# mlogger.net
KiCad netlist of a schematic drawn in EAGLE
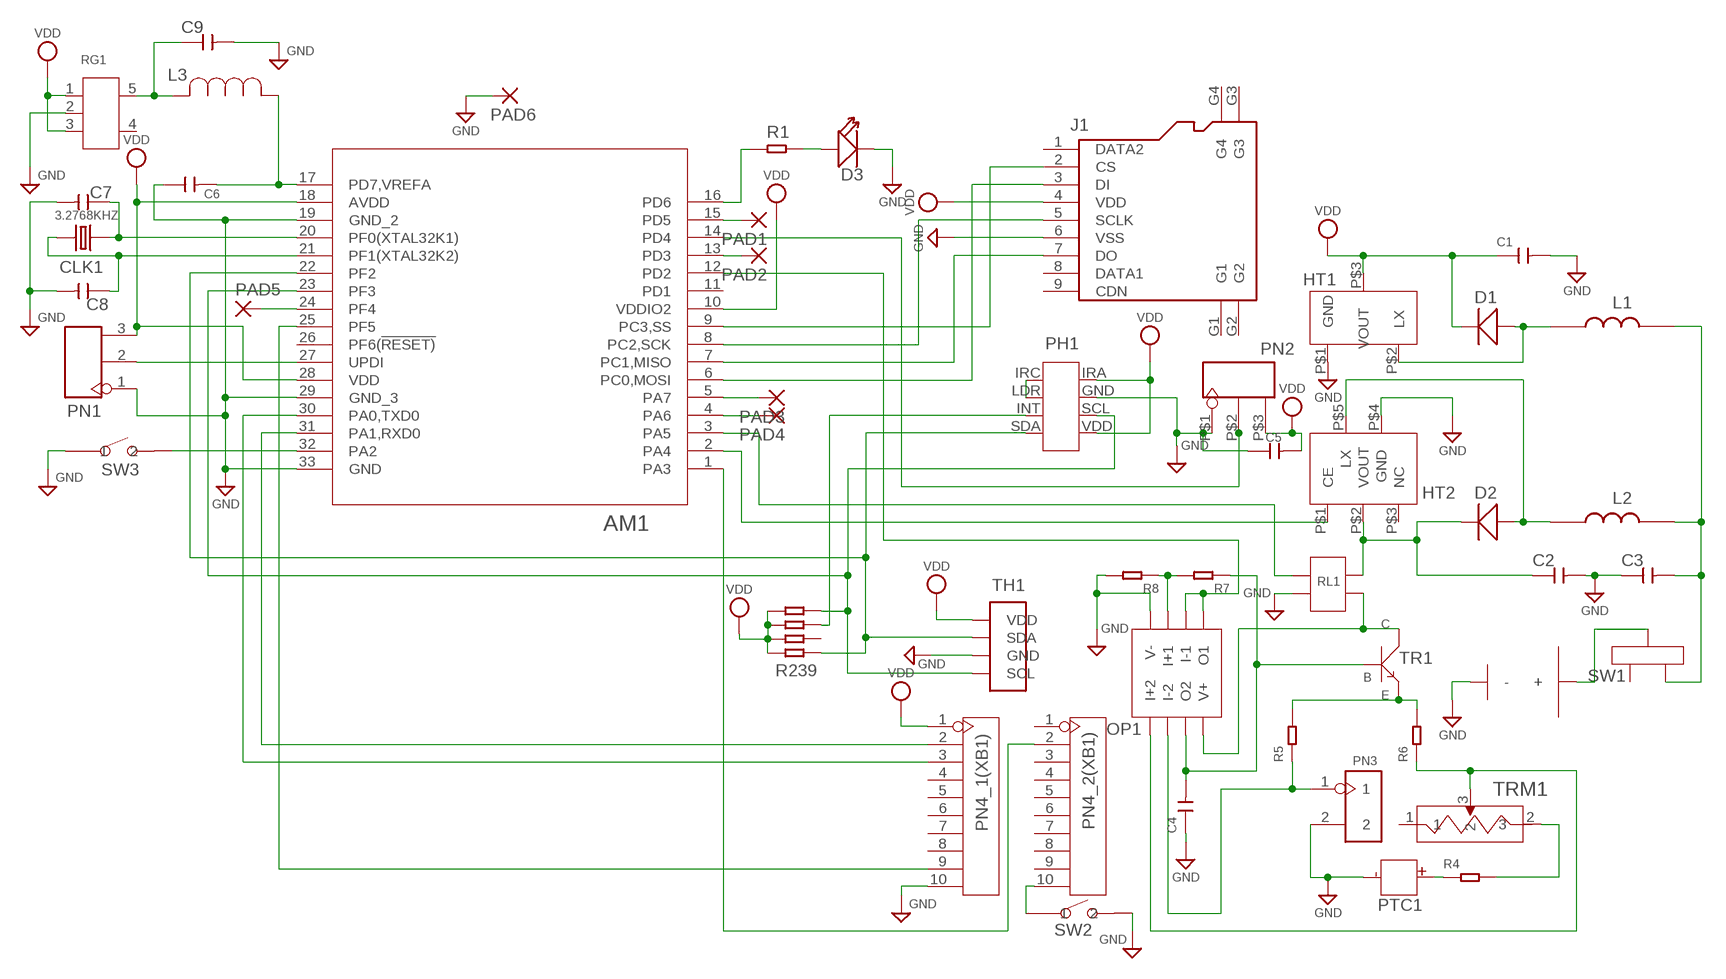
[diagram p0: schematic, sheet 1]

(export (version "E")
  (design (tool "Eeschema 10.0.6"))
  (components
    (comp (ref "AM1")
      (value "AVR64DB32-I/RXBVQFN32_RXB_MCH")
      (footprint "eagle-import:VQFN32_RXB_MCH")
      (fields
        (field (name "MANUFACTURER_PART_NUMBER") "AVR64DB32-I/RXB")
        (field (name "COPYRIGHT") "Copyright (C) 2022 Ultra Librarian. All rights reserved.")
      )
      (libsource (lib "eagle-import") (part "AVR64DB32-I/RXBVQFN32_RXB_MCH"))
    )
    (comp (ref "BB1")
      (value "BH321")
      (footprint "eagle-import:BH321")
      (libsource (lib "eagle-import") (part "BH321"))
    )
    (comp (ref "C1")
      (value "MURATA_0603")
      (footprint "eagle-import:C0603")
      (libsource (lib "eagle-import") (part "MURATA_0603"))
    )
    (comp (ref "C2")
      (value "MURATA_0603")
      (footprint "eagle-import:C0603")
      (libsource (lib "eagle-import") (part "MURATA_0603"))
    )
    (comp (ref "C3")
      (value "MURATA_0603")
      (footprint "eagle-import:C0603")
      (libsource (lib "eagle-import") (part "MURATA_0603"))
    )
    (comp (ref "C4")
      (value "MURATA_0603")
      (footprint "eagle-import:C0603")
      (libsource (lib "eagle-import") (part "MURATA_0603"))
    )
    (comp (ref "C5")
      (value "MURATA_0603")
      (footprint "eagle-import:C0603")
      (libsource (lib "eagle-import") (part "MURATA_0603"))
    )
    (comp (ref "C6")
      (value "MURATA_0603")
      (footprint "eagle-import:C0603")
      (libsource (lib "eagle-import") (part "MURATA_0603"))
    )
    (comp (ref "C7")
      (value "MURATA_0603")
      (footprint "eagle-import:C0603")
      (libsource (lib "eagle-import") (part "MURATA_0603"))
    )
    (comp (ref "C8")
      (value "MURATA_0603")
      (footprint "eagle-import:C0603")
      (libsource (lib "eagle-import") (part "MURATA_0603"))
    )
    (comp (ref "C9")
      (value "MURATA_0603")
      (footprint "eagle-import:C0603")
      (libsource (lib "eagle-import") (part "MURATA_0603"))
    )
    (comp (ref "CLK1")
      (value "3.2768KHZ")
      (footprint "eagle-import:X2-SMD-L2.0X1.2X0.55MM")
      (fields (field (name "MPN") "FC-12M"))
      (libsource (lib "eagle-import") (part "SMD-CRYSTAL-32.768KHZ-12.5PF-20PPM-90K(2P-L2.0X1.2MM)"))
    )
    (comp (ref "D1")
      (value "20V-1A")
      (footprint "eagle-import:SOD-123")
      (fields (field (name "MPN") "B5819W"))
      (libsource (lib "eagle-import") (part "SMD-DIODE-SCHOTTKY-20V-1A(SOD-123)"))
    )
    (comp (ref "D2")
      (value "20V-1A")
      (footprint "eagle-import:SOD-123")
      (fields (field (name "MPN") "B5819W"))
      (libsource (lib "eagle-import") (part "SMD-DIODE-SCHOTTKY-20V-1A(SOD-123)"))
    )
    (comp (ref "D3")
      (value "OSHR1608C1A")
      (footprint "eagle-import:C0603")
      (libsource (lib "eagle-import") (part "OSHR1608C1A"))
    )
    (comp (ref "HT1")
      (value "HT77XXSOT23")
      (footprint "eagle-import:HT77XXSOT23")
      (libsource (lib "eagle-import") (part "HT77XXSOT23"))
    )
    (comp (ref "HT2")
      (value "HT77XXSOT25")
      (footprint "eagle-import:HT77XXSOT25")
      (libsource (lib "eagle-import") (part "HT77XXSOT25"))
    )
    (comp (ref "J1")
      (value "MICROSD-9P")
      (footprint "eagle-import:MICRO-SD9+4P-SMD-16.1X14.5X1.85MM")
      (libsource (lib "eagle-import") (part "MICRO-SD-CARD-HOLDER-9P"))
    )
    (comp (ref "L1")
      (value "303010168_47UM_5X5MM")
      (footprint "eagle-import:L2018")
      (libsource (lib "eagle-import") (part "303010168_47UM_5X5MM"))
    )
    (comp (ref "L2")
      (value "303010168_47UM_5X5MM")
      (footprint "eagle-import:L2018")
      (libsource (lib "eagle-import") (part "303010168_47UM_5X5MM"))
    )
    (comp (ref "L3")
      (value "LBR2012T100KIND_TAIYO_LBR2012_TAY")
      (footprint "eagle-import:IND_TAIYO_LBR2012_TAY")
      (libsource (lib "eagle-import") (part "LBR2012T100KIND_TAIYO_LBR2012_TAY"))
    )
    (comp (ref "OP1")
      (value "NJM4565")
      (footprint "eagle-import:NJM4565")
      (libsource (lib "eagle-import") (part "NJM4565"))
    )
    (comp (ref "PAD1")
      (value "1,6/0,8")
      (footprint "eagle-import:1,6_0,8")
      (libsource (lib "eagle-import") (part "1,6/0,8"))
    )
    (comp (ref "PAD2")
      (value "1,6/0,8")
      (footprint "eagle-import:1,6_0,8")
      (libsource (lib "eagle-import") (part "1,6/0,8"))
    )
    (comp (ref "PAD3")
      (value "1,6/0,8")
      (footprint "eagle-import:1,6_0,8")
      (libsource (lib "eagle-import") (part "1,6/0,8"))
    )
    (comp (ref "PAD4")
      (value "1,6/0,8")
      (footprint "eagle-import:1,6_0,8")
      (libsource (lib "eagle-import") (part "1,6/0,8"))
    )
    (comp (ref "PAD5")
      (value "1,6/0,8")
      (footprint "eagle-import:1,6_0,8")
      (libsource (lib "eagle-import") (part "1,6/0,8"))
    )
    (comp (ref "PAD6")
      (value "1,6/0,8")
      (footprint "eagle-import:1,6_0,8")
      (libsource (lib "eagle-import") (part "1,6/0,8"))
    )
    (comp (ref "PH1")
      (value "VCNL4030X01")
      (footprint "eagle-import:VCNL4030X01")
      (libsource (lib "eagle-import") (part "VCNL4030X01"))
    )
    (comp (ref "PN1")
      (value "3p-2.54")
      (footprint "eagle-import:H3-2.54")
      (libsource (lib "eagle-import") (part "DIP-BLACK-MALE-HEADER-VERT(3P-2.54)"))
    )
    (comp (ref "PN2")
      (value "B3B-PH-K-S")
      (footprint "eagle-import:B3B-PH-K-S")
      (libsource (lib "eagle-import") (part "B3B-PH-K-S"))
    )
    (comp (ref "PN3")
      (value "2p-2.54")
      (footprint "eagle-import:H2-2.54")
      (fields (field (name "MPN") "RF130-1023ABS0741"))
      (libsource (lib "eagle-import") (part "DIP-BLACK-ROUND-FEMALE-HEADER-VERT(2P-2.54)"))
    )
    (comp (ref "PN4_1(XB1)")
      (value "10p-2.0")
      (footprint "eagle-import:H10-2.0")
      (fields (field (name "MPN") "F243-1110A1BSUA1"))
      (libsource (lib "eagle-import") (part "DIP-BLACK-FEMALE-HEADER-VERT(10P-2.0)"))
    )
    (comp (ref "PN4_2(XB1)")
      (value "10p-2.0")
      (footprint "eagle-import:H10-2.0")
      (fields (field (name "MPN") "F243-1110A1BSUA1"))
      (libsource (lib "eagle-import") (part "DIP-BLACK-FEMALE-HEADER-VERT(10P-2.0)"))
    )
    (comp (ref "PTC1")
      (value "TFPT1206")
      (footprint "eagle-import:TFPT1206")
      (libsource (lib "eagle-import") (part "TFPT1206"))
    )
    (comp (ref "R1")
      (value "RES_0603")
      (footprint "eagle-import:R0603")
      (libsource (lib "eagle-import") (part "RES_0603"))
    )
    (comp (ref "R4")
      (value "RES_0603")
      (footprint "eagle-import:R0603")
      (libsource (lib "eagle-import") (part "RES_0603"))
    )
    (comp (ref "R5")
      (value "RES_0603")
      (footprint "eagle-import:R0603")
      (libsource (lib "eagle-import") (part "RES_0603"))
    )
    (comp (ref "R6")
      (value "RES_0603")
      (footprint "eagle-import:R0603")
      (libsource (lib "eagle-import") (part "RES_0603"))
    )
    (comp (ref "R7")
      (value "RES_0603")
      (footprint "eagle-import:R0603")
      (libsource (lib "eagle-import") (part "RES_0603"))
    )
    (comp (ref "R8")
      (value "RES_0603")
      (footprint "eagle-import:R0603")
      (libsource (lib "eagle-import") (part "RES_0603"))
    )
    (comp (ref "R239")
      (value "R1005X4")
      (footprint "eagle-import:R1005X4")
      (libsource (lib "eagle-import") (part "R1005X4"))
    )
    (comp (ref "RG1")
      (value "TCR2EF20SOT-25___(SMV)_TOS")
      (footprint "eagle-import:SOT-25___(SMV)_TOS")
      (libsource (lib "eagle-import") (part "TCR2EF20SOT-25___(SMV)_TOS"))
    )
    (comp (ref "RL1")
      (value "CPC1002N")
      (footprint "eagle-import:CPC1002N")
      (libsource (lib "eagle-import") (part "CPC1002N"))
    )
    (comp (ref "SW1")
      (value "SS-12D00G3")
      (footprint "eagle-import:SS-12D00G3")
      (libsource (lib "eagle-import") (part "SS-12D00G3"))
    )
    (comp (ref "SW2")
      (value "TVAF06-A020B-R")
      (footprint "eagle-import:TVAF06-A020B-R")
      (libsource (lib "eagle-import") (part "TVAF06-A020B-R"))
    )
    (comp (ref "SW3")
      (value "TVAF06-A020B-R")
      (footprint "eagle-import:TVAF06-A020B-R")
      (libsource (lib "eagle-import") (part "TVAF06-A020B-R"))
    )
    (comp (ref "TH1")
      (value "AHT20")
      (footprint "eagle-import:AHT20")
      (libsource (lib "eagle-import") (part "AHT20"))
    )
    (comp (ref "TR1")
      (value "MMBTA42")
      (footprint "eagle-import:MMBTA42")
      (libsource (lib "eagle-import") (part "MMBTA42"))
    )
    (comp (ref "TRM1")
      (value "TC33X-1-103EIND_1-103E-L")
      (footprint "eagle-import:IND_1-103E-L")
      (libsource (lib "eagle-import") (part "TC33X-1-103EIND_1-103E-L"))
    )
  )
  (nets
    (net (code "1") (name "GND") (class "Default")
      (node (ref "AM1") (pin "19") (pinfunction "GND_2_19") (pintype "passive"))
      (node (ref "AM1") (pin "29") (pinfunction "GND_3_29") (pintype "passive"))
      (node (ref "AM1") (pin "33") (pinfunction "GND_33") (pintype "passive"))
      (node (ref "BB1") (pin "V-") (pinfunction "-_V-") (pintype "bidirectional"))
      (node (ref "C1") (pin "2") (pinfunction "2_2") (pintype "passive"))
      (node (ref "C2") (pin "2") (pinfunction "2_2") (pintype "passive"))
      (node (ref "C3") (pin "1") (pinfunction "1_1") (pintype "passive"))
      (node (ref "C4") (pin "1") (pinfunction "1_1") (pintype "passive"))
      (node (ref "C5") (pin "1") (pinfunction "1_1") (pintype "passive"))
      (node (ref "C6") (pin "1") (pinfunction "1_1") (pintype "passive"))
      (node (ref "C7") (pin "2") (pinfunction "2_2") (pintype "passive"))
      (node (ref "C8") (pin "2") (pinfunction "2_2") (pintype "passive"))
      (node (ref "C9") (pin "2") (pinfunction "2_2") (pintype "passive"))
      (node (ref "D3") (pin "2") (pinfunction "-_2") (pintype "passive"))
      (node (ref "HT1") (pin "P$1") (pinfunction "GND_P$1") (pintype "bidirectional"))
      (node (ref "HT2") (pin "P$4") (pinfunction "GND_P$4") (pintype "bidirectional"))
      (node (ref "J1") (pin "6") (pinfunction "VSS_6") (pintype "bidirectional"))
      (node (ref "OP1") (pin "P$4") (pinfunction "V-_P$4") (pintype "bidirectional"))
      (node (ref "PAD6") (pin "1") (pinfunction "P_1") (pintype "passive"))
      (node (ref "PH1") (pin "GND") (pinfunction "GND_GND") (pintype "bidirectional"))
      (node (ref "PN1") (pin "1") (pinfunction "P$1_1") (pintype "bidirectional"))
      (node (ref "PN2") (pin "P$1") (pinfunction "P$1_P$1") (pintype "bidirectional"))
      (node (ref "PN3") (pin "2") (pinfunction "2_2") (pintype "bidirectional"))
      (node (ref "PN4_1(XB1)") (pin "10") (pinfunction "10_10") (pintype "bidirectional"))
      (node (ref "PTC1") (pin "P$1") (pinfunction "P$1_P$1") (pintype "bidirectional"))
      (node (ref "R8") (pin "2") (pinfunction "2_2") (pintype "passive"))
      (node (ref "RG1") (pin "2") (pinfunction "2_2") (pintype "passive"))
      (node (ref "RL1") (pin "GND") (pinfunction "GND_GND") (pintype "bidirectional"))
      (node (ref "SW2") (pin "P$2") (pinfunction "2_P$2") (pintype "bidirectional"))
      (node (ref "SW3") (pin "P$1") (pinfunction "1_P$1") (pintype "bidirectional"))
      (node (ref "TH1") (pin "P$5") (pinfunction "GND_P$5") (pintype "bidirectional"))
    )
    (net (code "2") (name "Net-(AM1-PA0,TXD0)") (class "Default")
      (node (ref "AM1") (pin "30") (pinfunction "PA0,TXD0_30") (pintype "bidirectional"))
      (node (ref "PN4_1(XB1)") (pin "3") (pinfunction "3_3") (pintype "bidirectional"))
    )
    (net (code "3") (name "Net-(AM1-PA1,RXD0)") (class "Default")
      (node (ref "AM1") (pin "31") (pinfunction "PA1,RXD0_31") (pintype "bidirectional"))
      (node (ref "PN4_1(XB1)") (pin "2") (pinfunction "2_2") (pintype "bidirectional"))
    )
    (net (code "4") (name "Net-(AM1-PA2)") (class "Default")
      (node (ref "AM1") (pin "32") (pinfunction "PA2_32") (pintype "bidirectional"))
      (node (ref "SW3") (pin "P$2") (pinfunction "2_P$2") (pintype "bidirectional"))
    )
    (net (code "5") (name "Net-(AM1-PA3)") (class "Default")
      (node (ref "AM1") (pin "1") (pinfunction "PA3_1") (pintype "bidirectional"))
      (node (ref "PN4_2(XB1)") (pin "2") (pinfunction "2_2") (pintype "bidirectional"))
    )
    (net (code "6") (name "Net-(AM1-PA4)") (class "Default")
      (node (ref "AM1") (pin "2") (pinfunction "PA4_2") (pintype "bidirectional"))
      (node (ref "HT2") (pin "P$1") (pinfunction "CE_P$1") (pintype "bidirectional"))
    )
    (net (code "7") (name "Net-(AM1-PA5)") (class "Default")
      (node (ref "AM1") (pin "3") (pinfunction "PA5_3") (pintype "bidirectional"))
      (node (ref "RL1") (pin "+") (pinfunction "+_+") (pintype "bidirectional"))
    )
    (net (code "8") (name "Net-(AM1-PA6)") (class "Default")
      (node (ref "AM1") (pin "4") (pinfunction "PA6_4") (pintype "bidirectional"))
      (node (ref "PAD4") (pin "1") (pinfunction "P_1") (pintype "passive"))
    )
    (net (code "9") (name "Net-(AM1-PA7)") (class "Default")
      (node (ref "AM1") (pin "5") (pinfunction "PA7_5") (pintype "bidirectional"))
      (node (ref "PAD3") (pin "1") (pinfunction "P_1") (pintype "passive"))
    )
    (net (code "10") (name "Net-(AM1-PC0,MOSI)") (class "Default")
      (node (ref "AM1") (pin "6") (pinfunction "PC0,MOSI_6") (pintype "bidirectional"))
      (node (ref "J1") (pin "3") (pinfunction "DI_3") (pintype "bidirectional"))
    )
    (net (code "11") (name "Net-(AM1-PC1,MISO)") (class "Default")
      (node (ref "AM1") (pin "7") (pinfunction "PC1,MISO_7") (pintype "bidirectional"))
      (node (ref "J1") (pin "7") (pinfunction "DO_7") (pintype "bidirectional"))
    )
    (net (code "12") (name "Net-(AM1-PC2,SCK)") (class "Default")
      (node (ref "AM1") (pin "8") (pinfunction "PC2,SCK_8") (pintype "bidirectional"))
      (node (ref "J1") (pin "5") (pinfunction "SCLK_5") (pintype "bidirectional"))
    )
    (net (code "13") (name "Net-(AM1-PC3,SS)") (class "Default")
      (node (ref "AM1") (pin "9") (pinfunction "PC3,SS_9") (pintype "bidirectional"))
      (node (ref "J1") (pin "2") (pinfunction "CS_2") (pintype "bidirectional"))
    )
    (net (code "14") (name "Net-(AM1-PD2)") (class "Default")
      (node (ref "AM1") (pin "12") (pinfunction "PD2_12") (pintype "bidirectional"))
      (node (ref "OP1") (pin "P$1") (pinfunction "O1_P$1") (pintype "bidirectional"))
      (node (ref "OP1") (pin "P$2") (pinfunction "I-1_P$2") (pintype "bidirectional"))
    )
    (net (code "15") (name "Net-(AM1-PD3)") (class "Default")
      (node (ref "AM1") (pin "13") (pinfunction "PD3_13") (pintype "bidirectional"))
      (node (ref "PAD2") (pin "1") (pinfunction "P_1") (pintype "passive"))
    )
    (net (code "16") (name "Net-(AM1-PD4)") (class "Default")
      (node (ref "AM1") (pin "14") (pinfunction "PD4_14") (pintype "bidirectional"))
      (node (ref "PN2") (pin "P$2") (pinfunction "P$2_P$2") (pintype "bidirectional"))
    )
    (net (code "17") (name "Net-(AM1-PD5)") (class "Default")
      (node (ref "AM1") (pin "15") (pinfunction "PD5_15") (pintype "bidirectional"))
      (node (ref "PAD1") (pin "1") (pinfunction "P_1") (pintype "passive"))
    )
    (net (code "18") (name "Net-(AM1-PD6)") (class "Default")
      (node (ref "AM1") (pin "16") (pinfunction "PD6_16") (pintype "bidirectional"))
      (node (ref "R1") (pin "2") (pinfunction "2_2") (pintype "passive"))
    )
    (net (code "19") (name "Net-(AM1-PD7,VREFA)") (class "Default")
      (node (ref "AM1") (pin "17") (pinfunction "PD7,VREFA_17") (pintype "bidirectional"))
      (node (ref "C6") (pin "2") (pinfunction "2_2") (pintype "passive"))
      (node (ref "L3") (pin "1") (pinfunction "1_1") (pintype "passive"))
    )
    (net (code "20") (name "Net-(AM1-PF0(XTAL32K1))") (class "Default")
      (node (ref "AM1") (pin "20") (pinfunction "PF0(XTAL32K1)_20") (pintype "bidirectional"))
      (node (ref "C7") (pin "1") (pinfunction "1_1") (pintype "passive"))
      (node (ref "CLK1") (pin "1") (pinfunction "1_1") (pintype "passive"))
    )
    (net (code "21") (name "Net-(AM1-PF1(XTAL32K2))") (class "Default")
      (node (ref "AM1") (pin "21") (pinfunction "PF1(XTAL32K2)_21") (pintype "bidirectional"))
      (node (ref "C8") (pin "1") (pinfunction "1_1") (pintype "passive"))
      (node (ref "CLK1") (pin "2") (pinfunction "2_2") (pintype "passive"))
    )
    (net (code "22") (name "Net-(AM1-PF2)") (class "Default")
      (node (ref "AM1") (pin "22") (pinfunction "PF2_22") (pintype "bidirectional"))
      (node (ref "PH1") (pin "SDA") (pinfunction "SDA_SDA") (pintype "bidirectional"))
      (node (ref "R239") (pin "8") (pinfunction "8_8") (pintype "passive"))
      (node (ref "TH1") (pin "P$4") (pinfunction "SDA_P$4") (pintype "bidirectional"))
    )
    (net (code "23") (name "Net-(AM1-PF3)") (class "Default")
      (node (ref "AM1") (pin "23") (pinfunction "PF3_23") (pintype "bidirectional"))
      (node (ref "PH1") (pin "SCL") (pinfunction "SCL_SCL") (pintype "bidirectional"))
      (node (ref "R239") (pin "2") (pinfunction "2_2") (pintype "passive"))
      (node (ref "TH1") (pin "P$3") (pinfunction "SCL_P$3") (pintype "bidirectional"))
    )
    (net (code "24") (name "Net-(AM1-PF4)") (class "Default")
      (node (ref "AM1") (pin "24") (pinfunction "PF4_24") (pintype "bidirectional"))
      (node (ref "PAD5") (pin "1") (pinfunction "P_1") (pintype "passive"))
    )
    (net (code "25") (name "Net-(AM1-PF5)") (class "Default")
      (node (ref "AM1") (pin "25") (pinfunction "PF5_25") (pintype "bidirectional"))
      (node (ref "PN4_1(XB1)") (pin "9") (pinfunction "9_9") (pintype "bidirectional"))
    )
    (net (code "26") (name "Net-(AM1-UPDI)") (class "Default")
      (node (ref "AM1") (pin "27") (pinfunction "UPDI_27") (pintype "bidirectional"))
      (node (ref "PN1") (pin "2") (pinfunction "P$2_2") (pintype "bidirectional"))
    )
    (net (code "27") (name "Net-(BB1-+)") (class "Default")
      (node (ref "BB1") (pin "V+") (pinfunction "+_V+") (pintype "bidirectional"))
      (node (ref "SW1") (pin "P$1") (pinfunction "P2_P$1") (pintype "bidirectional"))
    )
    (net (code "28") (name "Net-(C9-Pad1)") (class "Default")
      (node (ref "C9") (pin "1") (pinfunction "1_1") (pintype "passive"))
      (node (ref "L3") (pin "2") (pinfunction "2_2") (pintype "passive"))
      (node (ref "RG1") (pin "5") (pinfunction "5_5") (pintype "power_in"))
    )
    (net (code "29") (name "Net-(D3-+)") (class "Default")
      (node (ref "D3") (pin "1") (pinfunction "+_1") (pintype "passive"))
      (node (ref "R1") (pin "1") (pinfunction "1_1") (pintype "passive"))
    )
    (net (code "30") (name "Net-(HT1-LX)") (class "Default")
      (node (ref "D1") (pin "+") (pinfunction "+_+") (pintype "passive"))
      (node (ref "HT1") (pin "P$2") (pinfunction "LX_P$2") (pintype "bidirectional"))
      (node (ref "L1") (pin "P$1") (pinfunction "P$1_P$1") (pintype "passive"))
    )
    (net (code "31") (name "Net-(HT2-LX)") (class "Default")
      (node (ref "D2") (pin "+") (pinfunction "+_+") (pintype "passive"))
      (node (ref "HT2") (pin "P$5") (pinfunction "LX_P$5") (pintype "bidirectional"))
      (node (ref "L2") (pin "P$1") (pinfunction "P$1_P$1") (pintype "passive"))
    )
    (net (code "32") (name "Net-(HT2-VOUT)") (class "Default")
      (node (ref "C2") (pin "1") (pinfunction "1_1") (pintype "passive"))
      (node (ref "D2") (pin "-") (pinfunction "-_-") (pintype "passive"))
      (node (ref "HT2") (pin "P$2") (pinfunction "VOUT_P$2") (pintype "bidirectional"))
      (node (ref "RL1") (pin "DC+") (pinfunction "DC+_DC+") (pintype "bidirectional"))
    )
    (net (code "33") (name "Net-(OP1-I+1)") (class "Default")
      (node (ref "OP1") (pin "P$3") (pinfunction "I+1_P$3") (pintype "bidirectional"))
      (node (ref "R7") (pin "2") (pinfunction "2_2") (pintype "passive"))
      (node (ref "R8") (pin "1") (pinfunction "1_1") (pintype "passive"))
    )
    (net (code "34") (name "Net-(OP1-I+2)") (class "Default")
      (node (ref "OP1") (pin "P$5") (pinfunction "I+2_P$5") (pintype "bidirectional"))
      (node (ref "R6") (pin "1") (pinfunction "1_1") (pintype "passive"))
      (node (ref "TRM1") (pin "3") (pinfunction "2_3") (pintype "passive"))
    )
    (net (code "35") (name "Net-(OP1-I-2)") (class "Default")
      (node (ref "OP1") (pin "P$6") (pinfunction "I-2_P$6") (pintype "bidirectional"))
      (node (ref "PN3") (pin "1") (pinfunction "1_1") (pintype "bidirectional"))
      (node (ref "R5") (pin "1") (pinfunction "1_1") (pintype "passive"))
    )
    (net (code "36") (name "Net-(OP1-O2)") (class "Default")
      (node (ref "C4") (pin "2") (pinfunction "2_2") (pintype "passive"))
      (node (ref "OP1") (pin "P$7") (pinfunction "O2_P$7") (pintype "bidirectional"))
      (node (ref "R7") (pin "1") (pinfunction "1_1") (pintype "passive"))
      (node (ref "TR1") (pin "P$1") (pinfunction "P$1_P$1") (pintype "bidirectional"))
    )
    (net (code "37") (name "Net-(OP1-V+)") (class "Default")
      (node (ref "OP1") (pin "P$8") (pinfunction "V+_P$8") (pintype "bidirectional"))
      (node (ref "RL1") (pin "DC-") (pinfunction "DC-_DC-") (pintype "bidirectional"))
      (node (ref "TR1") (pin "P$3") (pinfunction "C_P$3") (pintype "bidirectional"))
    )
    (net (code "38") (name "Net-(PH1-PadINT)") (class "Default")
      (node (ref "PH1") (pin "INT") (pinfunction "INT_INT") (pintype "bidirectional"))
      (node (ref "R239") (pin "4") (pinfunction "4_4") (pintype "passive"))
    )
    (net (code "39") (name "Net-(PH1-PadIRC)") (class "Default")
      (node (ref "PH1") (pin "IRC") (pinfunction "IRC_IRC") (pintype "bidirectional"))
      (node (ref "PH1") (pin "LDR") (pinfunction "LDR_LDR") (pintype "bidirectional"))
    )
    (net (code "40") (name "Net-(PTC1-PadP$2)") (class "Default")
      (node (ref "PTC1") (pin "P$2") (pinfunction "P$2_P$2") (pintype "bidirectional"))
      (node (ref "R4") (pin "1") (pinfunction "1_1") (pintype "passive"))
    )
    (net (code "41") (name "Net-(R5-Pad2)") (class "Default")
      (node (ref "R5") (pin "2") (pinfunction "2_2") (pintype "passive"))
      (node (ref "R6") (pin "2") (pinfunction "2_2") (pintype "passive"))
      (node (ref "TR1") (pin "P$2") (pinfunction "P$2_P$2") (pintype "bidirectional"))
    )
    (net (code "42") (name "Net-(SW1-P1)") (class "Default")
      (node (ref "C3") (pin "2") (pinfunction "2_2") (pintype "passive"))
      (node (ref "L1") (pin "P$2") (pinfunction "P$2_P$2") (pintype "passive"))
      (node (ref "L2") (pin "P$2") (pinfunction "P$2_P$2") (pintype "passive"))
      (node (ref "SW1") (pin "P$2") (pinfunction "P1_P$2") (pintype "bidirectional"))
    )
    (net (code "43") (name "Net-(SW2-1)") (class "Default")
      (node (ref "PN4_2(XB1)") (pin "10") (pinfunction "10_10") (pintype "bidirectional"))
      (node (ref "SW2") (pin "P$1") (pinfunction "1_P$1") (pintype "bidirectional"))
    )
    (net (code "44") (name "Net-(TRM1-3)") (class "Default")
      (node (ref "R4") (pin "2") (pinfunction "2_2") (pintype "passive"))
      (node (ref "TRM1") (pin "2") (pinfunction "3_2") (pintype "passive"))
    )
    (net (code "45") (name "VDD") (class "Default")
      (node (ref "AM1") (pin "10") (pinfunction "VDDIO2_10") (pintype "power_in"))
      (node (ref "AM1") (pin "18") (pinfunction "AVDD_18") (pintype "power_in"))
      (node (ref "AM1") (pin "28") (pinfunction "VDD_28") (pintype "power_in"))
      (node (ref "C1") (pin "1") (pinfunction "1_1") (pintype "passive"))
      (node (ref "C5") (pin "2") (pinfunction "2_2") (pintype "passive"))
      (node (ref "D1") (pin "-") (pinfunction "-_-") (pintype "passive"))
      (node (ref "HT1") (pin "P$3") (pinfunction "VOUT_P$3") (pintype "bidirectional"))
      (node (ref "J1") (pin "4") (pinfunction "VDD_4") (pintype "bidirectional"))
      (node (ref "PH1") (pin "IRA") (pinfunction "IRA_IRA") (pintype "bidirectional"))
      (node (ref "PH1") (pin "VDD") (pinfunction "VDD_VDD") (pintype "bidirectional"))
      (node (ref "PN1") (pin "3") (pinfunction "P$3_3") (pintype "bidirectional"))
      (node (ref "PN2") (pin "P$3") (pinfunction "P$3_P$3") (pintype "bidirectional"))
      (node (ref "PN4_1(XB1)") (pin "1") (pinfunction "1_1") (pintype "bidirectional"))
      (node (ref "R239") (pin "1") (pinfunction "1_1") (pintype "passive"))
      (node (ref "R239") (pin "3") (pinfunction "3_3") (pintype "passive"))
      (node (ref "R239") (pin "5") (pinfunction "5_5") (pintype "passive"))
      (node (ref "R239") (pin "7") (pinfunction "7_7") (pintype "passive"))
      (node (ref "RG1") (pin "1") (pinfunction "1_1") (pintype "power_in"))
      (node (ref "RG1") (pin "3") (pinfunction "3_3") (pintype "passive"))
      (node (ref "TH1") (pin "P$2") (pinfunction "VDD_P$2") (pintype "bidirectional"))
    )
    (net (code "46") (name "unconnected-(AM1-PD1-Pad11)") (class "Default")
      (node (ref "AM1") (pin "11") (pinfunction "PD1_11") (pintype "bidirectional"))
    )
    (net (code "47") (name "unconnected-(AM1-PF6(~{RESET})-Pad26)") (class "Default")
      (node (ref "AM1") (pin "26") (pinfunction "PF6(~{RESET})_26") (pintype "bidirectional"))
    )
    (net (code "48") (name "unconnected-(HT2-NC-PadP$3)") (class "Default")
      (node (ref "HT2") (pin "P$3") (pinfunction "NC_P$3") (pintype "bidirectional"))
    )
    (net (code "49") (name "unconnected-(J1-CDN-Pad9)") (class "Default")
      (node (ref "J1") (pin "9") (pinfunction "CDN_9") (pintype "bidirectional"))
    )
    (net (code "50") (name "unconnected-(J1-DATA1-Pad8)") (class "Default")
      (node (ref "J1") (pin "8") (pinfunction "DATA1_8") (pintype "bidirectional"))
    )
    (net (code "51") (name "unconnected-(J1-DATA2-Pad1)") (class "Default")
      (node (ref "J1") (pin "1") (pinfunction "DATA2_1") (pintype "bidirectional"))
    )
    (net (code "52") (name "unconnected-(J1-PadG1)") (class "Default")
      (node (ref "J1") (pin "G1") (pinfunction "G1_G1") (pintype "bidirectional"))
    )
    (net (code "53") (name "unconnected-(J1-PadG2)") (class "Default")
      (node (ref "J1") (pin "G2") (pinfunction "G2_G2") (pintype "bidirectional"))
    )
    (net (code "54") (name "unconnected-(J1-PadG3)") (class "Default")
      (node (ref "J1") (pin "G3") (pinfunction "G3_G3") (pintype "bidirectional"))
    )
    (net (code "55") (name "unconnected-(J1-PadG4)") (class "Default")
      (node (ref "J1") (pin "G4") (pinfunction "G4_G4") (pintype "bidirectional"))
    )
    (net (code "56") (name "unconnected-(PN4_1(XB1)-Pad4)") (class "Default")
      (node (ref "PN4_1(XB1)") (pin "4") (pinfunction "4_4") (pintype "bidirectional"))
    )
    (net (code "57") (name "unconnected-(PN4_1(XB1)-Pad5)") (class "Default")
      (node (ref "PN4_1(XB1)") (pin "5") (pinfunction "5_5") (pintype "bidirectional"))
    )
    (net (code "58") (name "unconnected-(PN4_1(XB1)-Pad6)") (class "Default")
      (node (ref "PN4_1(XB1)") (pin "6") (pinfunction "6_6") (pintype "bidirectional"))
    )
    (net (code "59") (name "unconnected-(PN4_1(XB1)-Pad7)") (class "Default")
      (node (ref "PN4_1(XB1)") (pin "7") (pinfunction "7_7") (pintype "bidirectional"))
    )
    (net (code "60") (name "unconnected-(PN4_1(XB1)-Pad8)") (class "Default")
      (node (ref "PN4_1(XB1)") (pin "8") (pinfunction "8_8") (pintype "bidirectional"))
    )
    (net (code "61") (name "unconnected-(PN4_2(XB1)-Pad1)") (class "Default")
      (node (ref "PN4_2(XB1)") (pin "1") (pinfunction "1_1") (pintype "bidirectional"))
    )
    (net (code "62") (name "unconnected-(PN4_2(XB1)-Pad3)") (class "Default")
      (node (ref "PN4_2(XB1)") (pin "3") (pinfunction "3_3") (pintype "bidirectional"))
    )
    (net (code "63") (name "unconnected-(PN4_2(XB1)-Pad4)") (class "Default")
      (node (ref "PN4_2(XB1)") (pin "4") (pinfunction "4_4") (pintype "bidirectional"))
    )
    (net (code "64") (name "unconnected-(PN4_2(XB1)-Pad5)") (class "Default")
      (node (ref "PN4_2(XB1)") (pin "5") (pinfunction "5_5") (pintype "bidirectional"))
    )
    (net (code "65") (name "unconnected-(PN4_2(XB1)-Pad6)") (class "Default")
      (node (ref "PN4_2(XB1)") (pin "6") (pinfunction "6_6") (pintype "bidirectional"))
    )
    (net (code "66") (name "unconnected-(PN4_2(XB1)-Pad7)") (class "Default")
      (node (ref "PN4_2(XB1)") (pin "7") (pinfunction "7_7") (pintype "bidirectional"))
    )
    (net (code "67") (name "unconnected-(PN4_2(XB1)-Pad8)") (class "Default")
      (node (ref "PN4_2(XB1)") (pin "8") (pinfunction "8_8") (pintype "bidirectional"))
    )
    (net (code "68") (name "unconnected-(PN4_2(XB1)-Pad9)") (class "Default")
      (node (ref "PN4_2(XB1)") (pin "9") (pinfunction "9_9") (pintype "bidirectional"))
    )
    (net (code "69") (name "unconnected-(R239-Pad6)") (class "Default")
      (node (ref "R239") (pin "6") (pinfunction "6_6") (pintype "passive"))
    )
    (net (code "70") (name "unconnected-(RG1-Pad4)") (class "Default")
      (node (ref "RG1") (pin "4") (pinfunction "4_4") (pintype "no_connect"))
    )
    (net (code "71") (name "unconnected-(SW1-P3-PadP$3)") (class "Default")
      (node (ref "SW1") (pin "P$3") (pinfunction "P3_P$3") (pintype "bidirectional"))
    )
    (net (code "72") (name "unconnected-(TRM1-Pad1)") (class "Default")
      (node (ref "TRM1") (pin "1") (pinfunction "1_1") (pintype "passive"))
    )
  )
)
